# lcmeter.net
KiCad netlist of a schematic drawn in EAGLE
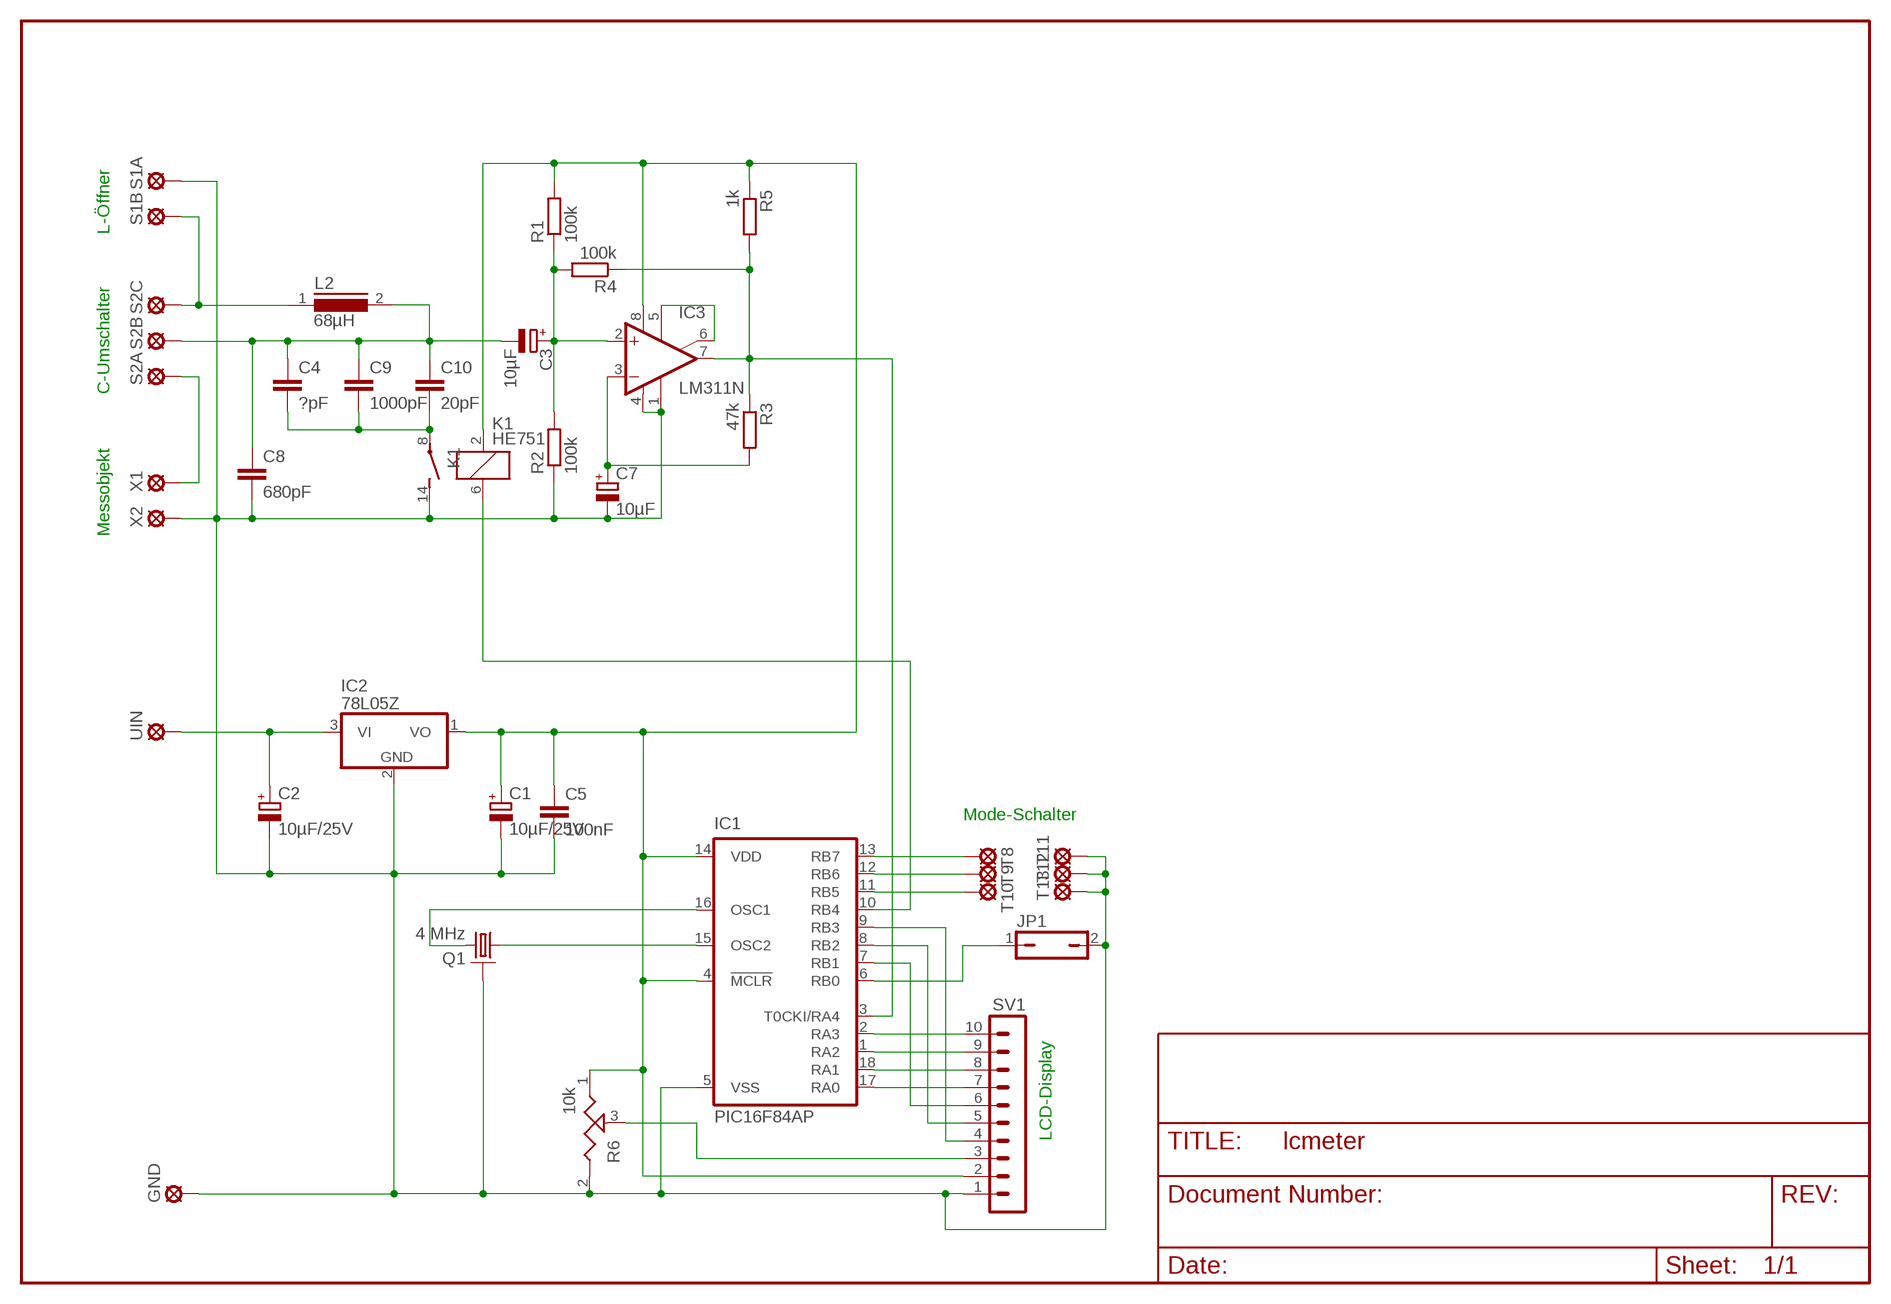
[diagram p0: schematic, sheet 1]

(export (version "E")
  (design (tool "Eeschema 10.0.6"))
  (components
    (comp (ref "C1")
      (value "10µF/25V")
      (footprint "eagle-import:E2,5-5")
      (libsource (lib "eagle-import") (part "CPOL-EUE2.5-5"))
    )
    (comp (ref "C2")
      (value "10µF/25V")
      (footprint "eagle-import:E2,5-5")
      (libsource (lib "eagle-import") (part "CPOL-EUE2.5-5"))
    )
    (comp (ref "C3")
      (value "10µF")
      (footprint "eagle-import:E5-10,5")
      (libsource (lib "eagle-import") (part "CPOL-EUE5-10.5"))
    )
    (comp (ref "C4")
      (value "?pF")
      (footprint "eagle-import:C150-054X183")
      (libsource (lib "eagle-import") (part "C-EU150-054X183"))
    )
    (comp (ref "C5")
      (value "100nF")
      (footprint "eagle-import:C050-050X075")
      (libsource (lib "eagle-import") (part "C-EU050-050X075"))
    )
    (comp (ref "C7")
      (value "10µF")
      (footprint "eagle-import:E5-10,5")
      (libsource (lib "eagle-import") (part "CPOL-EUE5-10.5"))
    )
    (comp (ref "C8")
      (value "680pF")
      (footprint "eagle-import:C150-054X183")
      (libsource (lib "eagle-import") (part "C-EU150-054X183"))
    )
    (comp (ref "C9")
      (value "1000pF")
      (footprint "eagle-import:C150-054X183")
      (libsource (lib "eagle-import") (part "C-EU150-054X183"))
    )
    (comp (ref "C10")
      (value "20pF")
      (footprint "eagle-import:C150-054X183")
      (libsource (lib "eagle-import") (part "C-EU150-054X183"))
    )
    (comp (ref "GND")
      (value "LSP10")
      (footprint "eagle-import:LSP10")
      (libsource (lib "eagle-import") (part "LSP10"))
    )
    (comp (ref "IC1")
      (value "PIC16F84AP")
      (footprint "eagle-import:DIL18")
      (libsource (lib "eagle-import") (part "PIC16F8P4A"))
    )
    (comp (ref "IC2")
      (value "78L05Z")
      (footprint "eagle-import:TO92")
      (libsource (lib "eagle-import") (part "78ZL05"))
    )
    (comp (ref "IC3")
      (value "LM311N")
      (footprint "eagle-import:DIL08")
      (libsource (lib "eagle-import") (part "LM311N"))
    )
    (comp (ref "JP1")
      (value "JP1Q")
      (footprint "eagle-import:JP1")
      (libsource (lib "eagle-import") (part "JP1Q"))
    )
    (comp (ref "K1")
      (value "HE751")
      (footprint "eagle-import:HE751")
      (libsource (lib "eagle-import") (part "HE751"))
    )
    (comp (ref "L2")
      (value "68µH")
      (footprint "eagle-import:MESC26")
      (libsource (lib "eagle-import") (part "MESC26"))
    )
    (comp (ref "Q1")
      (value "4 MHz")
      (footprint "eagle-import:RES3PIN")
      (libsource (lib "eagle-import") (part "RESONATOR"))
    )
    (comp (ref "R1")
      (value "100k")
      (footprint "eagle-import:0309_12")
      (libsource (lib "eagle-import") (part "R-EU_0309/12"))
    )
    (comp (ref "R2")
      (value "100k")
      (footprint "eagle-import:0309_12")
      (libsource (lib "eagle-import") (part "R-EU_0309/12"))
    )
    (comp (ref "R3")
      (value "47k")
      (footprint "eagle-import:0309_12")
      (libsource (lib "eagle-import") (part "R-EU_0309/12"))
    )
    (comp (ref "R4")
      (value "100k")
      (footprint "eagle-import:0309_12")
      (libsource (lib "eagle-import") (part "R-EU_0309/12"))
    )
    (comp (ref "R5")
      (value "1k")
      (footprint "eagle-import:0309_12")
      (libsource (lib "eagle-import") (part "R-EU_0309/12"))
    )
    (comp (ref "R6")
      (value "10k")
      (footprint "eagle-import:PT-10")
      (libsource (lib "eagle-import") (part "POTUS-L"))
    )
    (comp (ref "S1A")
      (value "LSP10")
      (footprint "eagle-import:LSP10")
      (libsource (lib "eagle-import") (part "LSP10"))
    )
    (comp (ref "S1B")
      (value "LSP10")
      (footprint "eagle-import:LSP10")
      (libsource (lib "eagle-import") (part "LSP10"))
    )
    (comp (ref "S2A")
      (value "LSP10")
      (footprint "eagle-import:LSP10")
      (libsource (lib "eagle-import") (part "LSP10"))
    )
    (comp (ref "S2B")
      (value "LSP10")
      (footprint "eagle-import:LSP10")
      (libsource (lib "eagle-import") (part "LSP10"))
    )
    (comp (ref "S2C")
      (value "LSP10")
      (footprint "eagle-import:LSP10")
      (libsource (lib "eagle-import") (part "LSP10"))
    )
    (comp (ref "SV1")
      (value "MA10-1")
      (footprint "eagle-import:MA10-1")
      (libsource (lib "eagle-import") (part "MA10-1"))
    )
    (comp (ref "T8")
      (value "LSP10")
      (footprint "eagle-import:LSP10")
      (libsource (lib "eagle-import") (part "LSP10"))
    )
    (comp (ref "T9")
      (value "LSP10")
      (footprint "eagle-import:LSP10")
      (libsource (lib "eagle-import") (part "LSP10"))
    )
    (comp (ref "T10")
      (value "LSP10")
      (footprint "eagle-import:LSP10")
      (libsource (lib "eagle-import") (part "LSP10"))
    )
    (comp (ref "T11")
      (value "LSP10")
      (footprint "eagle-import:LSP10")
      (libsource (lib "eagle-import") (part "LSP10"))
    )
    (comp (ref "T12")
      (value "LSP10")
      (footprint "eagle-import:LSP10")
      (libsource (lib "eagle-import") (part "LSP10"))
    )
    (comp (ref "T13")
      (value "LSP10")
      (footprint "eagle-import:LSP10")
      (libsource (lib "eagle-import") (part "LSP10"))
    )
    (comp (ref "UIN")
      (value "LSP10")
      (footprint "eagle-import:LSP10")
      (libsource (lib "eagle-import") (part "LSP10"))
    )
    (comp (ref "X1")
      (value "LCx1")
      (footprint "eagle-import:LSP10")
      (libsource (lib "eagle-import") (part "LSP10"))
    )
    (comp (ref "X2")
      (value "LSP10")
      (footprint "eagle-import:LSP10")
      (libsource (lib "eagle-import") (part "LSP10"))
    )
  )
  (nets
    (net (code "1") (name "Net-(C10-Pad1)") (class "Default")
      (node (ref "C10") (pin "1") (pinfunction "1_1") (pintype "passive"))
      (node (ref "C3") (pin "-") (pinfunction "-_-") (pintype "passive"))
      (node (ref "C4") (pin "1") (pinfunction "1_1") (pintype "passive"))
      (node (ref "C8") (pin "1") (pinfunction "1_1") (pintype "passive"))
      (node (ref "C9") (pin "1") (pinfunction "1_1") (pintype "passive"))
      (node (ref "L2") (pin "2") (pinfunction "2_2") (pintype "passive"))
      (node (ref "S2B") (pin "MP") (pinfunction "MP_MP") (pintype "passive"))
    )
    (net (code "2") (name "Net-(IC1-OSC1)") (class "Default")
      (node (ref "IC1") (pin "16") (pinfunction "OSC1_16") (pintype "input"))
      (node (ref "Q1") (pin "3") (pinfunction "2_3") (pintype "passive"))
    )
    (net (code "3") (name "Net-(IC1-OSC2)") (class "Default")
      (node (ref "IC1") (pin "15") (pinfunction "OSC2_15") (pintype "output"))
      (node (ref "Q1") (pin "1") (pinfunction "1_1") (pintype "passive"))
    )
    (net (code "4") (name "Net-(IC1-RA0)") (class "Default")
      (node (ref "IC1") (pin "17") (pinfunction "RA0_17") (pintype "bidirectional"))
      (node (ref "SV1") (pin "7") (pinfunction "7_7") (pintype "passive"))
    )
    (net (code "5") (name "Net-(IC1-RA1)") (class "Default")
      (node (ref "IC1") (pin "18") (pinfunction "RA1_18") (pintype "bidirectional"))
      (node (ref "SV1") (pin "8") (pinfunction "8_8") (pintype "passive"))
    )
    (net (code "6") (name "Net-(IC1-RA2)") (class "Default")
      (node (ref "IC1") (pin "1") (pinfunction "RA2_1") (pintype "bidirectional"))
      (node (ref "SV1") (pin "9") (pinfunction "9_9") (pintype "passive"))
    )
    (net (code "7") (name "Net-(IC1-RA3)") (class "Default")
      (node (ref "IC1") (pin "2") (pinfunction "RA3_2") (pintype "bidirectional"))
      (node (ref "SV1") (pin "10") (pinfunction "10_10") (pintype "passive"))
    )
    (net (code "8") (name "Net-(IC1-RB0)") (class "Default")
      (node (ref "IC1") (pin "6") (pinfunction "RB0_6") (pintype "bidirectional"))
      (node (ref "JP1") (pin "1") (pinfunction "1_1") (pintype "passive"))
    )
    (net (code "9") (name "Net-(IC1-RB1)") (class "Default")
      (node (ref "IC1") (pin "7") (pinfunction "RB1_7") (pintype "bidirectional"))
      (node (ref "SV1") (pin "6") (pinfunction "6_6") (pintype "passive"))
    )
    (net (code "10") (name "Net-(IC1-RB2)") (class "Default")
      (node (ref "IC1") (pin "8") (pinfunction "RB2_8") (pintype "bidirectional"))
      (node (ref "SV1") (pin "5") (pinfunction "5_5") (pintype "passive"))
    )
    (net (code "11") (name "Net-(IC1-RB3)") (class "Default")
      (node (ref "IC1") (pin "9") (pinfunction "RB3_9") (pintype "bidirectional"))
      (node (ref "SV1") (pin "4") (pinfunction "4_4") (pintype "passive"))
    )
    (net (code "12") (name "Net-(IC1-RB4)") (class "Default")
      (node (ref "IC1") (pin "10") (pinfunction "RB4_10") (pintype "bidirectional"))
      (node (ref "K1") (pin "6") (pinfunction "2_6") (pintype "passive"))
    )
    (net (code "13") (name "Net-(IC1-RB5)") (class "Default")
      (node (ref "IC1") (pin "11") (pinfunction "RB5_11") (pintype "bidirectional"))
      (node (ref "T10") (pin "MP") (pinfunction "MP_MP") (pintype "passive"))
    )
    (net (code "14") (name "Net-(IC1-RB6)") (class "Default")
      (node (ref "IC1") (pin "12") (pinfunction "RB6_12") (pintype "bidirectional"))
      (node (ref "T9") (pin "MP") (pinfunction "MP_MP") (pintype "passive"))
    )
    (net (code "15") (name "Net-(IC1-RB7)") (class "Default")
      (node (ref "IC1") (pin "13") (pinfunction "RB7_13") (pintype "bidirectional"))
      (node (ref "T8") (pin "MP") (pinfunction "MP_MP") (pintype "passive"))
    )
    (net (code "16") (name "Net-(IC1-T0CKI{slash}RA4)") (class "Default")
      (node (ref "IC1") (pin "3") (pinfunction "T0CKI/RA4_3") (pintype "bidirectional"))
      (node (ref "IC3") (pin "7") (pinfunction "OUT_7") (pintype "output"))
      (node (ref "R3") (pin "1") (pinfunction "1_1") (pintype "passive"))
      (node (ref "R4") (pin "1") (pinfunction "1_1") (pintype "passive"))
      (node (ref "R5") (pin "2") (pinfunction "2_2") (pintype "passive"))
    )
    (net (code "17") (name "Net-(IC1-VDD)") (class "Default")
      (node (ref "C1") (pin "+") (pinfunction "+_+") (pintype "passive"))
      (node (ref "C5") (pin "1") (pinfunction "1_1") (pintype "passive"))
      (node (ref "IC1") (pin "14") (pinfunction "VDD_14") (pintype "power_in"))
      (node (ref "IC1") (pin "4") (pinfunction "~{MCLR}_4") (pintype "input"))
      (node (ref "IC2") (pin "1") (pinfunction "VO_1") (pintype "passive"))
      (node (ref "IC3") (pin "8") (pinfunction "V+_8") (pintype "power_in"))
      (node (ref "K1") (pin "2") (pinfunction "1_2") (pintype "passive"))
      (node (ref "R1") (pin "2") (pinfunction "2_2") (pintype "passive"))
      (node (ref "R5") (pin "1") (pinfunction "1_1") (pintype "passive"))
      (node (ref "R6") (pin "1") (pinfunction "1_1") (pintype "passive"))
      (node (ref "SV1") (pin "2") (pinfunction "2_2") (pintype "passive"))
    )
    (net (code "18") (name "Net-(IC1-VSS)") (class "Default")
      (node (ref "C1") (pin "-") (pinfunction "-_-") (pintype "passive"))
      (node (ref "C2") (pin "-") (pinfunction "-_-") (pintype "passive"))
      (node (ref "C5") (pin "2") (pinfunction "2_2") (pintype "passive"))
      (node (ref "C7") (pin "-") (pinfunction "-_-") (pintype "passive"))
      (node (ref "C8") (pin "2") (pinfunction "2_2") (pintype "passive"))
      (node (ref "GND") (pin "MP") (pinfunction "MP_MP") (pintype "passive"))
      (node (ref "IC1") (pin "5") (pinfunction "VSS_5") (pintype "power_in"))
      (node (ref "IC2") (pin "2") (pinfunction "GND_2") (pintype "passive"))
      (node (ref "IC3") (pin "1") (pinfunction "GND_1") (pintype "passive"))
      (node (ref "IC3") (pin "4") (pinfunction "V-_4") (pintype "power_in"))
      (node (ref "JP1") (pin "2") (pinfunction "2_2") (pintype "passive"))
      (node (ref "K1") (pin "14") (pinfunction "S_14") (pintype "passive"))
      (node (ref "Q1") (pin "2") (pinfunction "3_2") (pintype "passive"))
      (node (ref "R2") (pin "1") (pinfunction "1_1") (pintype "passive"))
      (node (ref "R6") (pin "2") (pinfunction "2_2") (pintype "passive"))
      (node (ref "S1A") (pin "MP") (pinfunction "MP_MP") (pintype "passive"))
      (node (ref "SV1") (pin "1") (pinfunction "1_1") (pintype "passive"))
      (node (ref "T11") (pin "MP") (pinfunction "MP_MP") (pintype "passive"))
      (node (ref "T12") (pin "MP") (pinfunction "MP_MP") (pintype "passive"))
      (node (ref "T13") (pin "MP") (pinfunction "MP_MP") (pintype "passive"))
      (node (ref "X2") (pin "MP") (pinfunction "MP_MP") (pintype "passive"))
    )
    (net (code "19") (name "Net-(IC2-VI)") (class "Default")
      (node (ref "C2") (pin "+") (pinfunction "+_+") (pintype "passive"))
      (node (ref "IC2") (pin "3") (pinfunction "VI_3") (pintype "input"))
      (node (ref "UIN") (pin "MP") (pinfunction "MP_MP") (pintype "passive"))
    )
    (net (code "20") (name "Net-(IC3-+IN)") (class "Default")
      (node (ref "C3") (pin "+") (pinfunction "+_+") (pintype "passive"))
      (node (ref "IC3") (pin "2") (pinfunction "+IN_2") (pintype "input"))
      (node (ref "R1") (pin "1") (pinfunction "1_1") (pintype "passive"))
      (node (ref "R2") (pin "2") (pinfunction "2_2") (pintype "passive"))
      (node (ref "R4") (pin "2") (pinfunction "2_2") (pintype "passive"))
    )
    (net (code "21") (name "Net-(IC3--IN)") (class "Default")
      (node (ref "C7") (pin "+") (pinfunction "+_+") (pintype "passive"))
      (node (ref "IC3") (pin "3") (pinfunction "-IN_3") (pintype "input"))
      (node (ref "R3") (pin "2") (pinfunction "2_2") (pintype "passive"))
    )
    (net (code "22") (name "Net-(IC3-ON)") (class "Default")
      (node (ref "IC3") (pin "5") (pinfunction "ON_5") (pintype "passive"))
      (node (ref "IC3") (pin "6") (pinfunction "ON/STR_6") (pintype "passive"))
    )
    (net (code "23") (name "Net-(K1B-P)") (class "Default")
      (node (ref "C10") (pin "2") (pinfunction "2_2") (pintype "passive"))
      (node (ref "C4") (pin "2") (pinfunction "2_2") (pintype "passive"))
      (node (ref "C9") (pin "2") (pinfunction "2_2") (pintype "passive"))
      (node (ref "K1") (pin "8") (pinfunction "P_8") (pintype "passive"))
    )
    (net (code "24") (name "Net-(L2-Pad1)") (class "Default")
      (node (ref "L2") (pin "1") (pinfunction "1_1") (pintype "passive"))
      (node (ref "S1B") (pin "MP") (pinfunction "MP_MP") (pintype "passive"))
      (node (ref "S2C") (pin "MP") (pinfunction "MP_MP") (pintype "passive"))
    )
    (net (code "25") (name "Net-(R6-Pad3)") (class "Default")
      (node (ref "R6") (pin "3") (pinfunction "3_3") (pintype "passive"))
      (node (ref "SV1") (pin "3") (pinfunction "3_3") (pintype "passive"))
    )
    (net (code "26") (name "Net-(S2A-PadMP)") (class "Default")
      (node (ref "S2A") (pin "MP") (pinfunction "MP_MP") (pintype "passive"))
      (node (ref "X1") (pin "MP") (pinfunction "MP_MP") (pintype "passive"))
    )
  )
)
